# kicker.net
KiCad netlist of a schematic drawn in EAGLE
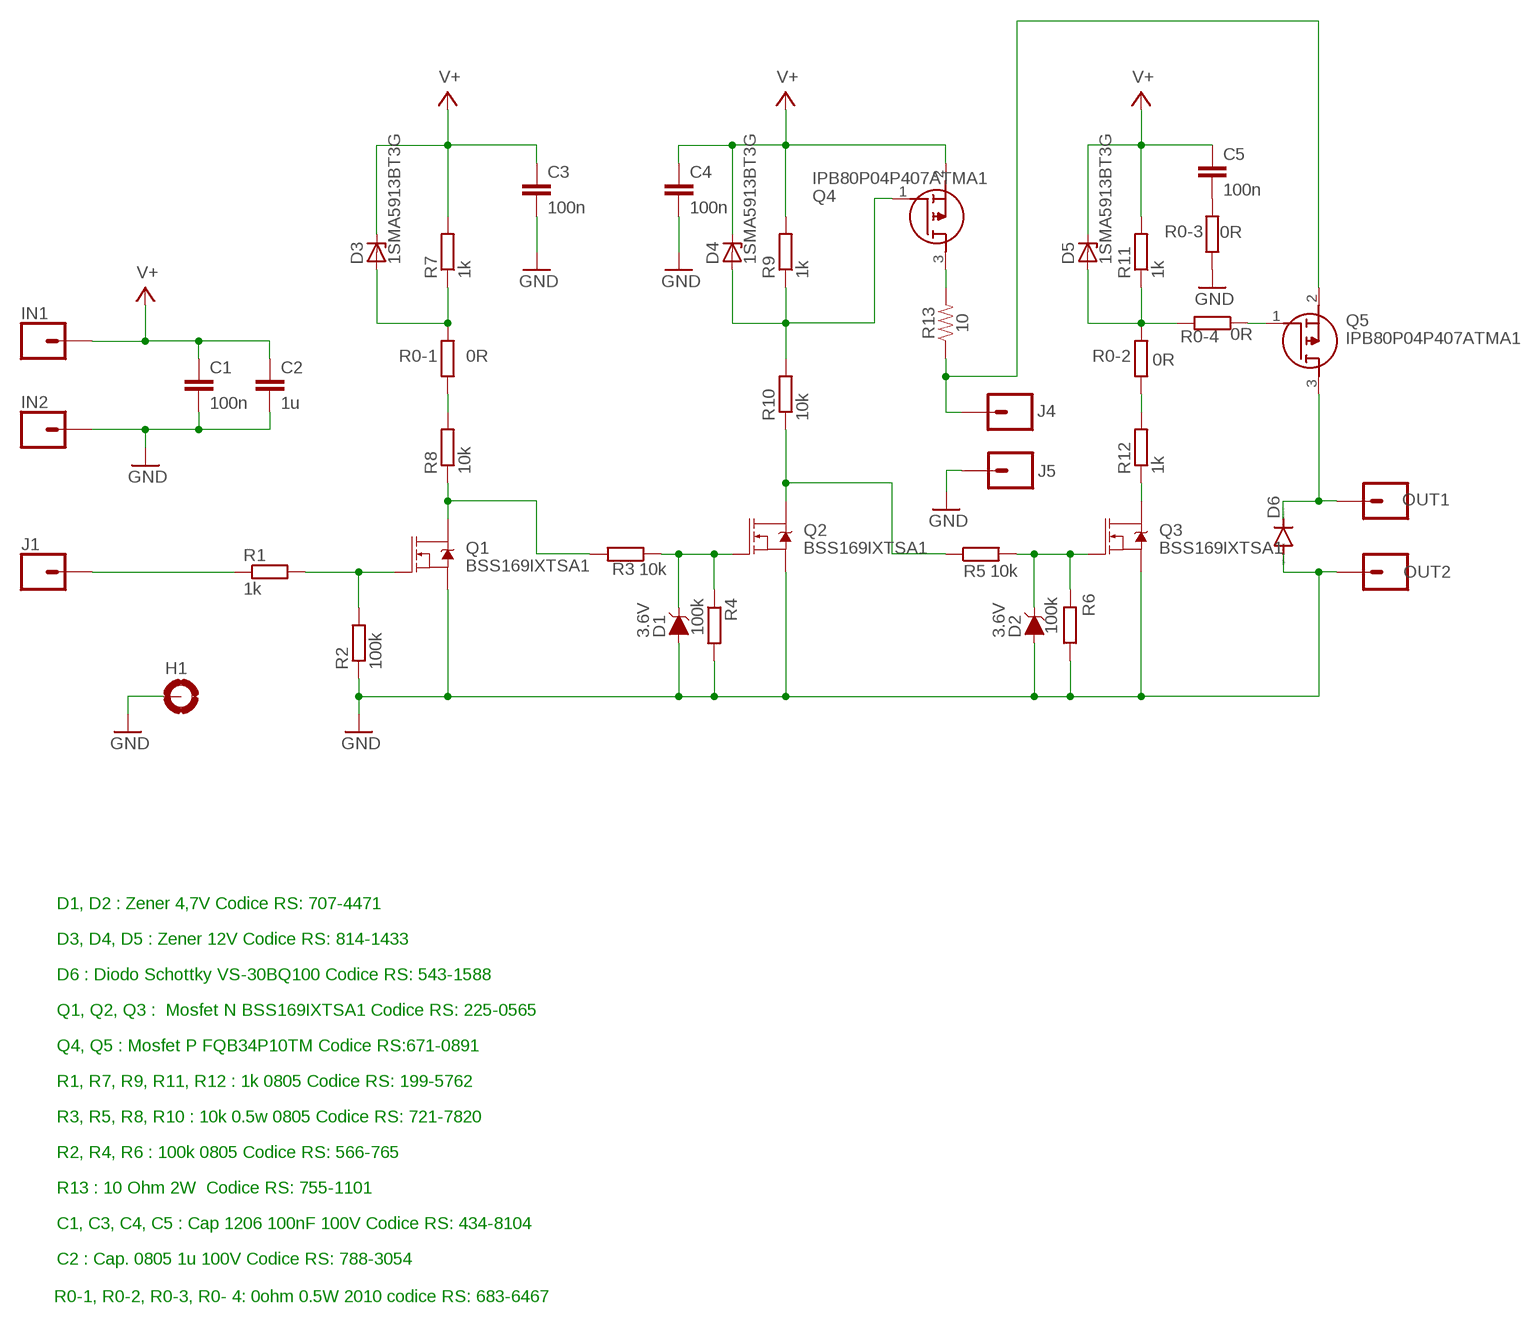
[diagram p0: schematic, sheet 1]

(export (version "E")
  (design (tool "Eeschema 10.0.6"))
  (components
    (comp (ref "C1")
      (value "100n")
      (footprint "eagle-import:C1206")
      (libsource (lib "eagle-import") (part "C-EUC1206"))
    )
    (comp (ref "C2")
      (value "1u")
      (footprint "eagle-import:C1206")
      (libsource (lib "eagle-import") (part "C-EUC1206"))
    )
    (comp (ref "C3")
      (value "100n")
      (footprint "eagle-import:C1206")
      (libsource (lib "eagle-import") (part "C-EUC1206"))
    )
    (comp (ref "C4")
      (value "100n")
      (footprint "eagle-import:C1206")
      (libsource (lib "eagle-import") (part "C-EUC1206"))
    )
    (comp (ref "C5")
      (value "100n")
      (footprint "eagle-import:C1206")
      (libsource (lib "eagle-import") (part "C-EUC1206"))
    )
    (comp (ref "D1")
      (value "3.6V")
      (footprint "eagle-import:SOD-323")
      (libsource (lib "eagle-import") (part "DIODE-ZENER-BZT52C3V6S"))
    )
    (comp (ref "D2")
      (value "3.6V")
      (footprint "eagle-import:SOD-323")
      (libsource (lib "eagle-import") (part "DIODE-ZENER-BZT52C3V6S"))
    )
    (comp (ref "D3")
      (value "1SMA5913BT3G")
      (footprint "eagle-import:DO214AC")
      (fields (field (name "MF") "ON Semiconductor"))
      (libsource (lib "eagle-import") (part "1SMA59BT3G13"))
    )
    (comp (ref "D4")
      (value "1SMA5913BT3G")
      (footprint "eagle-import:DO214AC")
      (fields (field (name "MF") "ON Semiconductor"))
      (libsource (lib "eagle-import") (part "1SMA59BT3G13"))
    )
    (comp (ref "D5")
      (value "1SMA5913BT3G")
      (footprint "eagle-import:DO214AC")
      (fields (field (name "MF") "ON Semiconductor"))
      (libsource (lib "eagle-import") (part "1SMA59BT3G13"))
    )
    (comp (ref "D6")
      (value "DIODE-SMC")
      (footprint "eagle-import:SMC")
      (libsource (lib "eagle-import") (part "DIODE-SMC"))
    )
    (comp (ref "H1")
      (value "MOUNT-PAD-ROUND3.0")
      (footprint "eagle-import:3,0-PAD")
      (libsource (lib "eagle-import") (part "MOUNT-PAD-ROUND3.0"))
    )
    (comp (ref "IN1")
      (value "CONN_01")
      (footprint "eagle-import:1X01")
      (libsource (lib "eagle-import") (part "CONN_01"))
    )
    (comp (ref "IN2")
      (value "CONN_01")
      (footprint "eagle-import:1X01")
      (libsource (lib "eagle-import") (part "CONN_01"))
    )
    (comp (ref "J1")
      (value "CONN_01")
      (footprint "eagle-import:1X01")
      (libsource (lib "eagle-import") (part "CONN_01"))
    )
    (comp (ref "J4")
      (value "CONN_01")
      (footprint "eagle-import:1X01")
      (libsource (lib "eagle-import") (part "CONN_01"))
    )
    (comp (ref "J5")
      (value "CONN_01")
      (footprint "eagle-import:1X01")
      (libsource (lib "eagle-import") (part "CONN_01"))
    )
    (comp (ref "OUT1")
      (value "CONN_01")
      (footprint "eagle-import:1X01")
      (libsource (lib "eagle-import") (part "CONN_01"))
    )
    (comp (ref "OUT2")
      (value "CONN_01")
      (footprint "eagle-import:1X01")
      (libsource (lib "eagle-import") (part "CONN_01"))
    )
    (comp (ref "Q1")
      (value "BSS169IXTSA1")
      (footprint "eagle-import:SOT23-3")
      (libsource (lib "eagle-import") (part "MOSFET-NCH-AO3404A"))
    )
    (comp (ref "Q2")
      (value "BSS169IXTSA1")
      (footprint "eagle-import:SOT23-3")
      (libsource (lib "eagle-import") (part "MOSFET-NCH-AO3404A"))
    )
    (comp (ref "Q3")
      (value "BSS169IXTSA1")
      (footprint "eagle-import:SOT23-3")
      (libsource (lib "eagle-import") (part "MOSFET-NCH-AO3404A"))
    )
    (comp (ref "Q4")
      (value "IPB80P04P407ATMA1")
      (footprint "eagle-import:PG-TO263-3-2_1")
      (fields (field (name "RS_PART_NUMBER") "8269487P"))
      (libsource (lib "eagle-import") (part "IPB80P04P407ATMA1"))
    )
    (comp (ref "Q5")
      (value "IPB80P04P407ATMA1")
      (footprint "eagle-import:PG-TO263-3-2_1")
      (fields (field (name "RS_PART_NUMBER") "8269487P"))
      (libsource (lib "eagle-import") (part "IPB80P04P407ATMA1"))
    )
    (comp (ref "R0-1")
      (value "0R")
      (footprint "eagle-import:R2010")
      (libsource (lib "eagle-import") (part "R-EU_R2010"))
    )
    (comp (ref "R0-2")
      (value "0R")
      (footprint "eagle-import:R2010")
      (libsource (lib "eagle-import") (part "R-EU_R2010"))
    )
    (comp (ref "R0-3")
      (value "0R")
      (footprint "eagle-import:R2010")
      (libsource (lib "eagle-import") (part "R-EU_R2010"))
    )
    (comp (ref "R0-4")
      (value "0R")
      (footprint "eagle-import:R2010")
      (libsource (lib "eagle-import") (part "R-EU_R2010"))
    )
    (comp (ref "R1")
      (value "1k")
      (footprint "eagle-import:R1206")
      (libsource (lib "eagle-import") (part "R-EU_R1206"))
    )
    (comp (ref "R2")
      (value "100k")
      (footprint "eagle-import:R1206")
      (libsource (lib "eagle-import") (part "R-EU_R1206"))
    )
    (comp (ref "R3")
      (value "10k")
      (footprint "eagle-import:R1206")
      (libsource (lib "eagle-import") (part "R-EU_R1206"))
    )
    (comp (ref "R4")
      (value "100k")
      (footprint "eagle-import:R1206")
      (libsource (lib "eagle-import") (part "R-EU_R1206"))
    )
    (comp (ref "R5")
      (value "10k")
      (footprint "eagle-import:R1206")
      (libsource (lib "eagle-import") (part "R-EU_R1206"))
    )
    (comp (ref "R6")
      (value "100k")
      (footprint "eagle-import:R1206")
      (libsource (lib "eagle-import") (part "R-EU_R1206"))
    )
    (comp (ref "R7")
      (value "1k")
      (footprint "eagle-import:R1206")
      (libsource (lib "eagle-import") (part "R-EU_R1206"))
    )
    (comp (ref "R8")
      (value "10k")
      (footprint "eagle-import:R1206")
      (libsource (lib "eagle-import") (part "R-EU_R1206"))
    )
    (comp (ref "R9")
      (value "1k")
      (footprint "eagle-import:R1206")
      (libsource (lib "eagle-import") (part "R-EU_R1206"))
    )
    (comp (ref "R10")
      (value "10k")
      (footprint "eagle-import:R1206")
      (libsource (lib "eagle-import") (part "R-EU_R1206"))
    )
    (comp (ref "R11")
      (value "1k")
      (footprint "eagle-import:R1206")
      (libsource (lib "eagle-import") (part "R-EU_R1206"))
    )
    (comp (ref "R12")
      (value "1k")
      (footprint "eagle-import:R1206")
      (libsource (lib "eagle-import") (part "R-EU_R1206"))
    )
    (comp (ref "R13")
      (value "10")
      (footprint "eagle-import:1210")
      (libsource (lib "eagle-import") (part "0.1OHM-1210-1/2W-1%"))
    )
  )
  (nets
    (net (code "1") (name "GND") (class "Default")
      (node (ref "C1") (pin "2") (pinfunction "2_2") (pintype "passive"))
      (node (ref "C2") (pin "2") (pinfunction "2_2") (pintype "passive"))
      (node (ref "C3") (pin "2") (pinfunction "2_2") (pintype "passive"))
      (node (ref "C4") (pin "2") (pinfunction "2_2") (pintype "passive"))
      (node (ref "D1") (pin "A") (pinfunction "A_A") (pintype "passive"))
      (node (ref "D2") (pin "A") (pinfunction "A_A") (pintype "passive"))
      (node (ref "D6") (pin "A") (pinfunction "A_A") (pintype "passive"))
      (node (ref "H1") (pin "B3,0") (pinfunction "MOUNT_B3,0") (pintype "passive"))
      (node (ref "IN2") (pin "1") (pinfunction "1_1") (pintype "passive"))
      (node (ref "J5") (pin "1") (pinfunction "1_1") (pintype "passive"))
      (node (ref "OUT2") (pin "1") (pinfunction "1_1") (pintype "passive"))
      (node (ref "Q1") (pin "2") (pinfunction "S_2") (pintype "bidirectional"))
      (node (ref "Q2") (pin "2") (pinfunction "S_2") (pintype "bidirectional"))
      (node (ref "Q3") (pin "2") (pinfunction "S_2") (pintype "bidirectional"))
      (node (ref "R0-3") (pin "1") (pinfunction "1_1") (pintype "passive"))
      (node (ref "R2") (pin "1") (pinfunction "1_1") (pintype "passive"))
      (node (ref "R4") (pin "2") (pinfunction "2_2") (pintype "passive"))
      (node (ref "R6") (pin "1") (pinfunction "1_1") (pintype "passive"))
    )
    (net (code "2") (name "Net-(C5-Pad2)") (class "Default")
      (node (ref "C5") (pin "2") (pinfunction "2_2") (pintype "passive"))
      (node (ref "R0-3") (pin "2") (pinfunction "2_2") (pintype "passive"))
    )
    (net (code "3") (name "Net-(D3-PadA)") (class "Default")
      (node (ref "D3") (pin "A") (pinfunction "A_A") (pintype "passive"))
      (node (ref "R0-1") (pin "2") (pinfunction "2_2") (pintype "passive"))
      (node (ref "R7") (pin "1") (pinfunction "1_1") (pintype "passive"))
    )
    (net (code "4") (name "Net-(D5-PadA)") (class "Default")
      (node (ref "D5") (pin "A") (pinfunction "A_A") (pintype "passive"))
      (node (ref "R0-2") (pin "2") (pinfunction "2_2") (pintype "passive"))
      (node (ref "R0-4") (pin "2") (pinfunction "2_2") (pintype "passive"))
      (node (ref "R11") (pin "1") (pinfunction "1_1") (pintype "passive"))
    )
    (net (code "5") (name "Net-(J1-Pad1)") (class "Default")
      (node (ref "J1") (pin "1") (pinfunction "1_1") (pintype "passive"))
      (node (ref "R1") (pin "1") (pinfunction "1_1") (pintype "passive"))
    )
    (net (code "6") (name "Net-(Q1-D)") (class "Default")
      (node (ref "Q1") (pin "3") (pinfunction "D_3") (pintype "bidirectional"))
      (node (ref "R3") (pin "2") (pinfunction "2_2") (pintype "passive"))
      (node (ref "R8") (pin "1") (pinfunction "1_1") (pintype "passive"))
    )
    (net (code "7") (name "Net-(Q1-G)") (class "Default")
      (node (ref "Q1") (pin "1") (pinfunction "G_1") (pintype "bidirectional"))
      (node (ref "R1") (pin "2") (pinfunction "2_2") (pintype "passive"))
      (node (ref "R2") (pin "2") (pinfunction "2_2") (pintype "passive"))
    )
    (net (code "8") (name "Net-(Q2-D)") (class "Default")
      (node (ref "Q2") (pin "3") (pinfunction "D_3") (pintype "bidirectional"))
      (node (ref "R10") (pin "1") (pinfunction "1_1") (pintype "passive"))
      (node (ref "R5") (pin "1") (pinfunction "1_1") (pintype "passive"))
    )
    (net (code "9") (name "Net-(Q2-G)") (class "Default")
      (node (ref "D1") (pin "C") (pinfunction "C_C") (pintype "passive"))
      (node (ref "Q2") (pin "1") (pinfunction "G_1") (pintype "bidirectional"))
      (node (ref "R3") (pin "1") (pinfunction "1_1") (pintype "passive"))
      (node (ref "R4") (pin "1") (pinfunction "1_1") (pintype "passive"))
    )
    (net (code "10") (name "Net-(Q3-D)") (class "Default")
      (node (ref "Q3") (pin "3") (pinfunction "D_3") (pintype "bidirectional"))
      (node (ref "R12") (pin "1") (pinfunction "1_1") (pintype "passive"))
    )
    (net (code "11") (name "Net-(Q3-G)") (class "Default")
      (node (ref "D2") (pin "C") (pinfunction "C_C") (pintype "passive"))
      (node (ref "Q3") (pin "1") (pinfunction "G_1") (pintype "bidirectional"))
      (node (ref "R5") (pin "2") (pinfunction "2_2") (pintype "passive"))
      (node (ref "R6") (pin "2") (pinfunction "2_2") (pintype "passive"))
    )
    (net (code "12") (name "Net-(Q4-D)") (class "Default")
      (node (ref "Q4") (pin "3") (pinfunction "D_3") (pintype "bidirectional"))
      (node (ref "R13") (pin "2") (pinfunction "2_2") (pintype "passive"))
    )
    (net (code "13") (name "Net-(Q4-G)") (class "Default")
      (node (ref "D4") (pin "A") (pinfunction "A_A") (pintype "passive"))
      (node (ref "Q4") (pin "1") (pinfunction "G_1") (pintype "bidirectional"))
      (node (ref "R10") (pin "2") (pinfunction "2_2") (pintype "passive"))
      (node (ref "R9") (pin "1") (pinfunction "1_1") (pintype "passive"))
    )
    (net (code "14") (name "Net-(Q5-D)") (class "Default")
      (node (ref "D6") (pin "C") (pinfunction "C_C") (pintype "passive"))
      (node (ref "OUT1") (pin "1") (pinfunction "1_1") (pintype "passive"))
      (node (ref "Q5") (pin "3") (pinfunction "D_3") (pintype "bidirectional"))
    )
    (net (code "15") (name "Net-(Q5-G)") (class "Default")
      (node (ref "Q5") (pin "1") (pinfunction "G_1") (pintype "bidirectional"))
      (node (ref "R0-4") (pin "1") (pinfunction "1_1") (pintype "passive"))
    )
    (net (code "16") (name "Net-(Q5-S)") (class "Default")
      (node (ref "J4") (pin "1") (pinfunction "1_1") (pintype "passive"))
      (node (ref "Q5") (pin "2") (pinfunction "S_2") (pintype "bidirectional"))
      (node (ref "R13") (pin "1") (pinfunction "1_1") (pintype "passive"))
    )
    (net (code "17") (name "Net-(R0-1-Pad1)") (class "Default")
      (node (ref "R0-1") (pin "1") (pinfunction "1_1") (pintype "passive"))
      (node (ref "R8") (pin "2") (pinfunction "2_2") (pintype "passive"))
    )
    (net (code "18") (name "Net-(R0-2-Pad1)") (class "Default")
      (node (ref "R0-2") (pin "1") (pinfunction "1_1") (pintype "passive"))
      (node (ref "R12") (pin "2") (pinfunction "2_2") (pintype "passive"))
    )
    (net (code "19") (name "V+") (class "Default")
      (node (ref "C1") (pin "1") (pinfunction "1_1") (pintype "passive"))
      (node (ref "C2") (pin "1") (pinfunction "1_1") (pintype "passive"))
      (node (ref "C3") (pin "1") (pinfunction "1_1") (pintype "passive"))
      (node (ref "C4") (pin "1") (pinfunction "1_1") (pintype "passive"))
      (node (ref "C5") (pin "1") (pinfunction "1_1") (pintype "passive"))
      (node (ref "D3") (pin "C") (pinfunction "C_C") (pintype "passive"))
      (node (ref "D4") (pin "C") (pinfunction "C_C") (pintype "passive"))
      (node (ref "D5") (pin "C") (pinfunction "C_C") (pintype "passive"))
      (node (ref "IN1") (pin "1") (pinfunction "1_1") (pintype "passive"))
      (node (ref "Q4") (pin "2") (pinfunction "S_2") (pintype "bidirectional"))
      (node (ref "R11") (pin "2") (pinfunction "2_2") (pintype "passive"))
      (node (ref "R7") (pin "2") (pinfunction "2_2") (pintype "passive"))
      (node (ref "R9") (pin "2") (pinfunction "2_2") (pintype "passive"))
    )
  )
)
